# doodle_with_onboard_clock.net
KiCad netlist of a schematic drawn in EAGLE
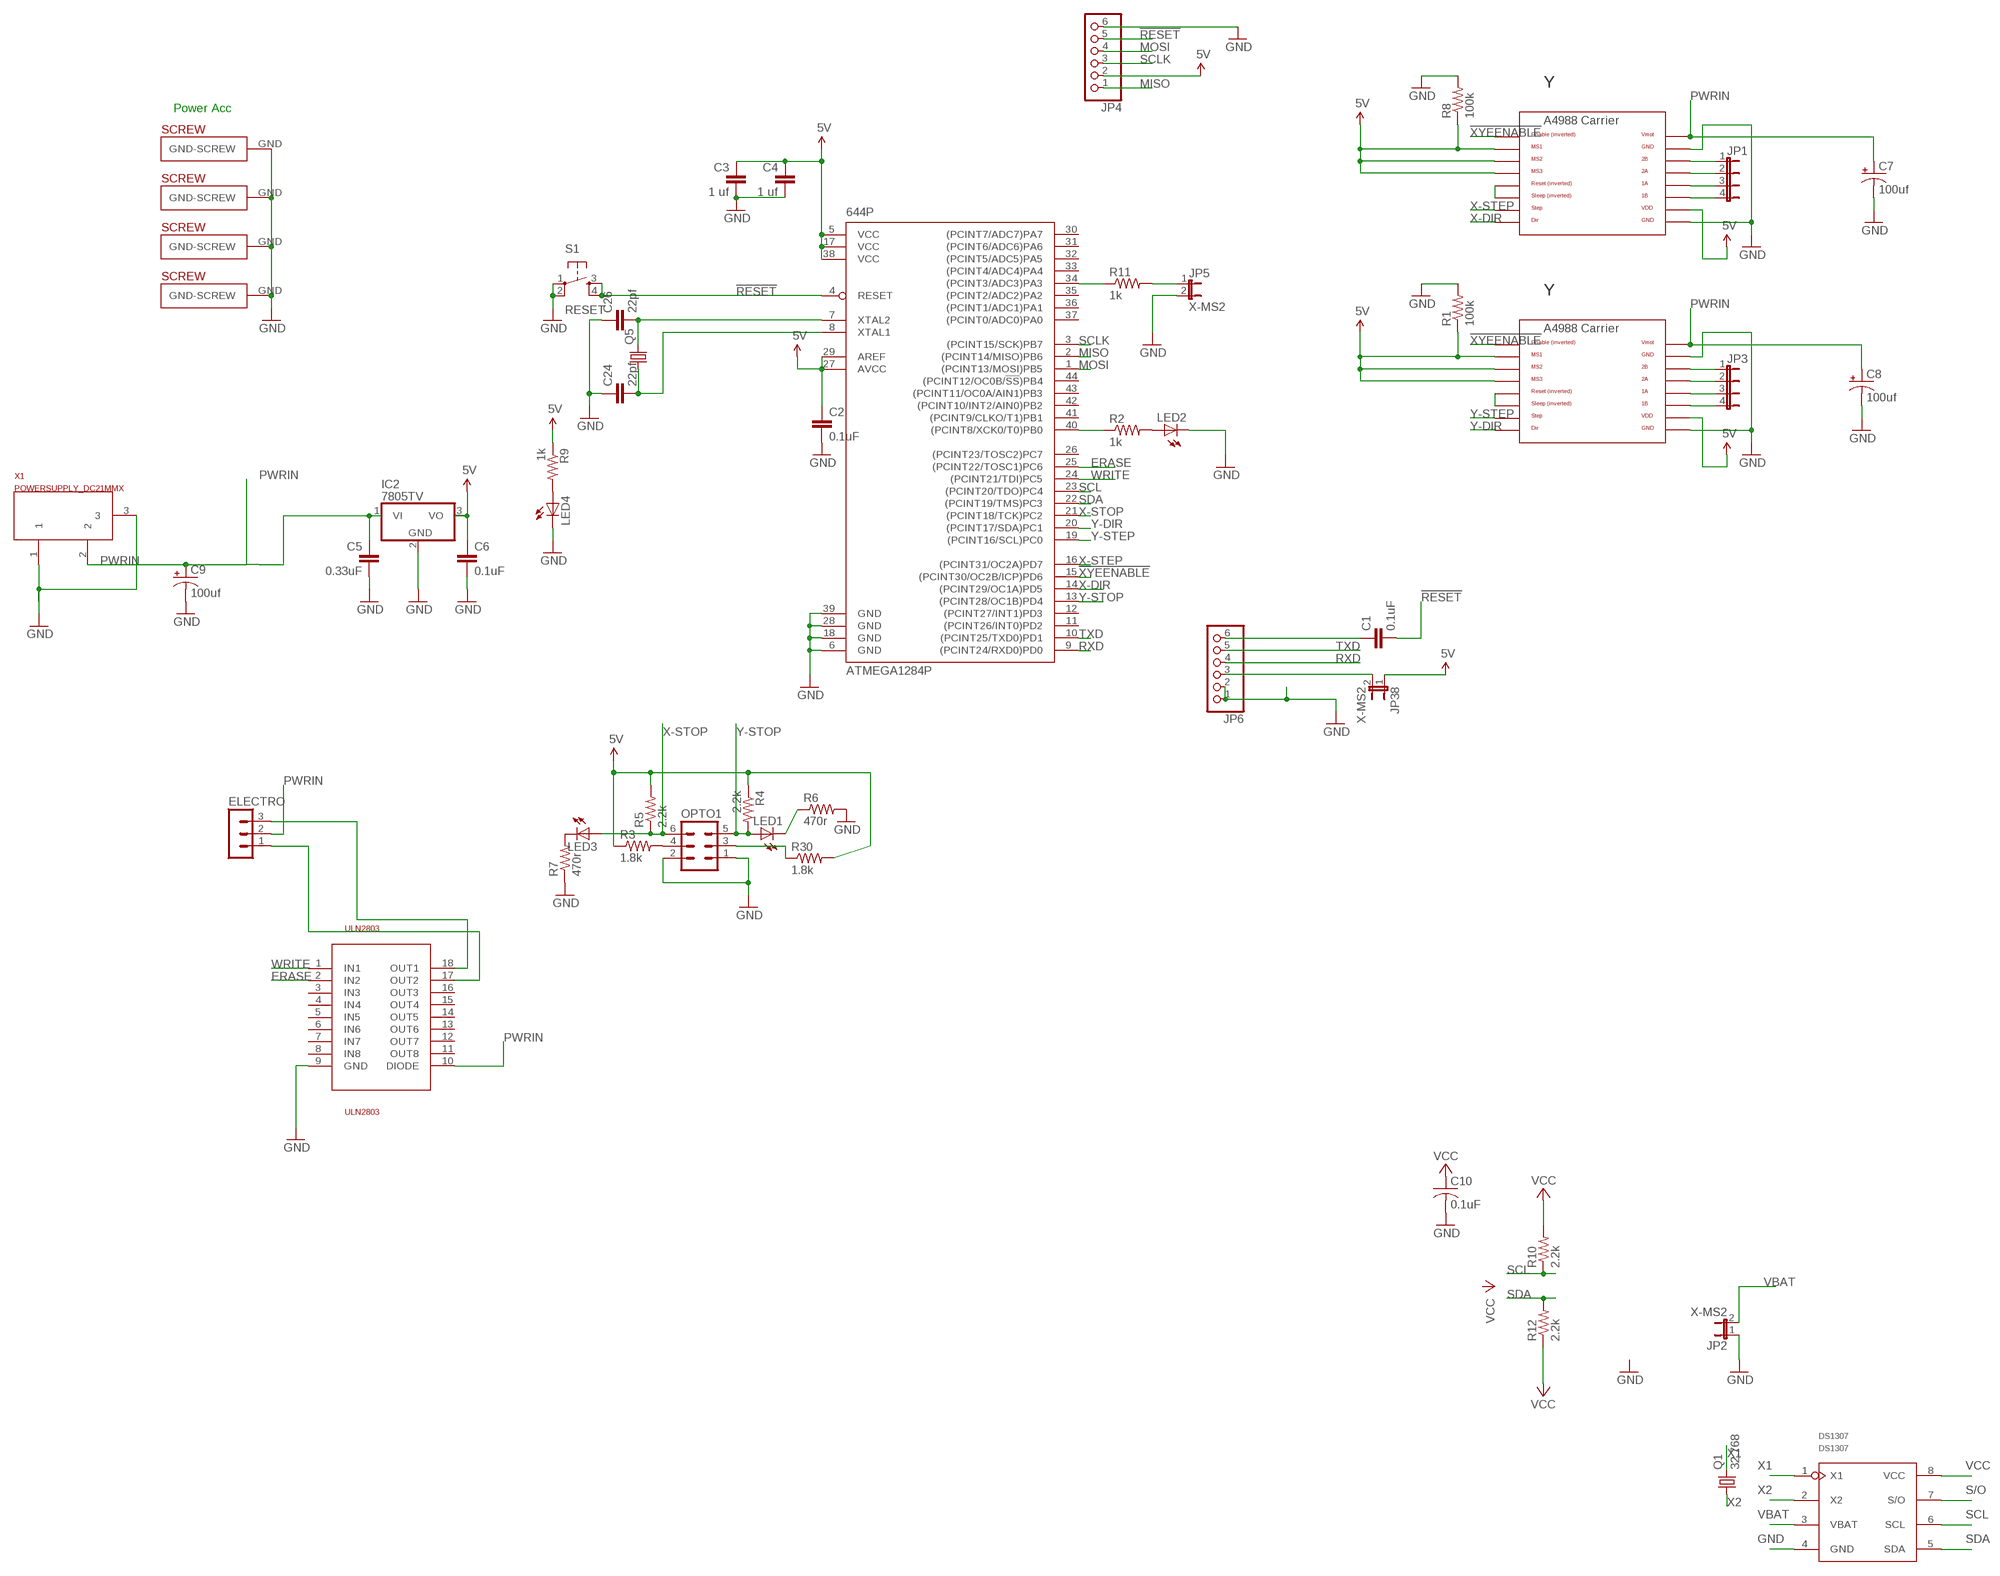
[diagram p0: schematic, sheet 1]

(export (version "E")
  (design (tool "Eeschema 10.0.6"))
  (components
    (comp (ref "644P")
      (value "ATMEGA1284P")
      (footprint "eagle-import:TQFP44")
      (fields (field (name "MPN") "ATMEGA644PV-10AU"))
      (libsource (lib "eagle-import") (part "ATMEGA644A"))
    )
    (comp (ref "C1")
      (value "0.1uF")
      (footprint "eagle-import:0805")
      (libsource (lib "eagle-import") (part "CAP0805"))
    )
    (comp (ref "C2")
      (value "0.1uF")
      (footprint "eagle-import:0805")
      (libsource (lib "eagle-import") (part "CAP0805"))
    )
    (comp (ref "C3")
      (value "1 uf")
      (footprint "eagle-import:0805")
      (libsource (lib "eagle-import") (part "CAP0805"))
    )
    (comp (ref "C4")
      (value "1 uf")
      (footprint "eagle-import:0805")
      (libsource (lib "eagle-import") (part "CAP0805"))
    )
    (comp (ref "C5")
      (value "0.33uF")
      (footprint "eagle-import:CAP-PTH-SMALL2")
      (libsource (lib "eagle-import") (part "CAPPTH2"))
    )
    (comp (ref "C6")
      (value "0.1uF")
      (footprint "eagle-import:CAP-PTH-SMALL2")
      (libsource (lib "eagle-import") (part "CAPPTH2"))
    )
    (comp (ref "C7")
      (value "100uf")
      (footprint "eagle-import:CPOL-RADIAL-100UF-25V")
      (libsource (lib "eagle-import") (part "CAP_POLPTH1"))
    )
    (comp (ref "C8")
      (value "100uf")
      (footprint "eagle-import:CPOL-RADIAL-100UF-25V")
      (libsource (lib "eagle-import") (part "CAP_POLPTH1"))
    )
    (comp (ref "C9")
      (value "100uf")
      (footprint "eagle-import:CPOL-RADIAL-100UF-25V")
      (libsource (lib "eagle-import") (part "CAP_POLPTH1"))
    )
    (comp (ref "C10")
      (value "0.1uF")
      (footprint "eagle-import:C0805")
      (libsource (lib "eagle-import") (part "C-USC0805"))
    )
    (comp (ref "C24")
      (value "22pf")
      (footprint "eagle-import:0805")
      (libsource (lib "eagle-import") (part "CAP0805"))
    )
    (comp (ref "C26")
      (value "22pf")
      (footprint "eagle-import:0805")
      (libsource (lib "eagle-import") (part "CAP0805"))
    )
    (comp (ref "DS1307")
      (value "DS1307")
      (footprint "eagle-import:SO08")
      (libsource (lib "eagle-import") (part "DS1307"))
    )
    (comp (ref "ELECTRO")
      (value "MA03-1")
      (footprint "eagle-import:MA03-1")
      (libsource (lib "eagle-import") (part "MA03-1"))
    )
    (comp (ref "IC2")
      (value "7805TV")
      (footprint "eagle-import:TO220V")
      (libsource (lib "eagle-import") (part "78TV05"))
    )
    (comp (ref "JP1")
      (value "JP4E")
      (footprint "eagle-import:JP4")
      (libsource (lib "eagle-import") (part "JP4E"))
    )
    (comp (ref "JP2")
      (value "X-MS2")
      (footprint "eagle-import:1X02")
      (libsource (lib "eagle-import") (part "JUMPER-2PTH"))
    )
    (comp (ref "JP3")
      (value "JP4E")
      (footprint "eagle-import:JP4")
      (libsource (lib "eagle-import") (part "JP4E"))
    )
    (comp (ref "JP4")
      (value "PINHD-1X6/90")
      (footprint "eagle-import:1X06_90")
      (libsource (lib "eagle-import") (part "PINHD-1X6/90"))
    )
    (comp (ref "JP5")
      (value "X-MS2")
      (footprint "eagle-import:1X02")
      (libsource (lib "eagle-import") (part "JUMPER-2PTH"))
    )
    (comp (ref "JP6")
      (value "PINHD-1X6")
      (footprint "eagle-import:1X06")
      (libsource (lib "eagle-import") (part "PINHD-1X6"))
    )
    (comp (ref "JP38")
      (value "X-MS2")
      (footprint "eagle-import:1X02")
      (libsource (lib "eagle-import") (part "JUMPER-2PTH"))
    )
    (comp (ref "LED1")
      (value "LEDCHIPLED_0805")
      (footprint "eagle-import:CHIPLED_0805")
      (libsource (lib "eagle-import") (part "LEDCHIPLED_0805"))
    )
    (comp (ref "LED2")
      (value "LEDCHIPLED_0805")
      (footprint "eagle-import:CHIPLED_0805")
      (libsource (lib "eagle-import") (part "LEDCHIPLED_0805"))
    )
    (comp (ref "LED3")
      (value "LEDCHIPLED_0805")
      (footprint "eagle-import:CHIPLED_0805")
      (libsource (lib "eagle-import") (part "LEDCHIPLED_0805"))
    )
    (comp (ref "LED4")
      (value "LEDCHIPLED_0805")
      (footprint "eagle-import:CHIPLED_0805")
      (libsource (lib "eagle-import") (part "LEDCHIPLED_0805"))
    )
    (comp (ref "OPTO1")
      (value "MA03-2")
      (footprint "eagle-import:MA03-2")
      (libsource (lib "eagle-import") (part "MA03-2"))
    )
    (comp (ref "Q1")
      (value "32.768")
      (footprint "eagle-import:TC38H")
      (libsource (lib "eagle-import") (part "CRYTALTC38H"))
    )
    (comp (ref "Q5")
      (value "CRYSTALHC49S")
      (footprint "eagle-import:HC49_S")
      (libsource (lib "eagle-import") (part "CRYSTALHC49S"))
    )
    (comp (ref "R1")
      (value "100k")
      (footprint "eagle-import:0207_7")
      (libsource (lib "eagle-import") (part "R-US_0207/7"))
    )
    (comp (ref "R2")
      (value "1k")
      (footprint "eagle-import:R0805")
      (libsource (lib "eagle-import") (part "resistor_R-US_R0805"))
    )
    (comp (ref "R3")
      (value "1.8k")
      (footprint "eagle-import:R0805")
      (libsource (lib "eagle-import") (part "resistor_R-US_R0805"))
    )
    (comp (ref "R4")
      (value "2.2k")
      (footprint "eagle-import:R0805")
      (libsource (lib "eagle-import") (part "resistor_R-US_R0805"))
    )
    (comp (ref "R5")
      (value "2.2k")
      (footprint "eagle-import:R0805")
      (libsource (lib "eagle-import") (part "resistor_R-US_R0805"))
    )
    (comp (ref "R6")
      (value "470r")
      (footprint "eagle-import:R0805")
      (libsource (lib "eagle-import") (part "resistor_R-US_R0805"))
    )
    (comp (ref "R7")
      (value "470r")
      (footprint "eagle-import:R0805")
      (libsource (lib "eagle-import") (part "resistor_R-US_R0805"))
    )
    (comp (ref "R8")
      (value "100k")
      (footprint "eagle-import:0207_7")
      (libsource (lib "eagle-import") (part "R-US_0207/7"))
    )
    (comp (ref "R9")
      (value "1k")
      (footprint "eagle-import:R0805")
      (libsource (lib "eagle-import") (part "resistor_R-US_R0805"))
    )
    (comp (ref "R10")
      (value "2.2k")
      (footprint "eagle-import:R0805")
      (libsource (lib "eagle-import") (part "resistor_R-US_R0805"))
    )
    (comp (ref "R11")
      (value "1k")
      (footprint "eagle-import:R0805")
      (libsource (lib "eagle-import") (part "resistor_R-US_R0805"))
    )
    (comp (ref "R12")
      (value "2.2k")
      (footprint "eagle-import:R0805")
      (libsource (lib "eagle-import") (part "resistor_R-US_R0805"))
    )
    (comp (ref "R30")
      (value "1.8k")
      (footprint "eagle-import:R0603")
      (libsource (lib "eagle-import") (part "resistor_R-US_R0603"))
    )
    (comp (ref "S1")
      (value "RESET")
      (footprint "eagle-import:TACTILE-PTH")
      (libsource (lib "eagle-import") (part "TAC_SWITCHPTH"))
    )
    (comp (ref "U$1")
      (value "A4988BREAKOUT")
      (footprint "eagle-import:A4988BREAKOUT")
      (libsource (lib "eagle-import") (part "A4988BREAKOUT"))
    )
    (comp (ref "U$7")
      (value "A4988BREAKOUT")
      (footprint "eagle-import:A4988BREAKOUT")
      (libsource (lib "eagle-import") (part "A4988BREAKOUT"))
    )
    (comp (ref "U$14")
      (value "PLATED-SCREW")
      (footprint "eagle-import:PLATEDSCREW")
      (libsource (lib "eagle-import") (part "PLATED-SCREW"))
    )
    (comp (ref "U$17")
      (value "PLATED-SCREW")
      (footprint "eagle-import:PLATEDSCREW")
      (libsource (lib "eagle-import") (part "PLATED-SCREW"))
    )
    (comp (ref "U$18")
      (value "PLATED-SCREW")
      (footprint "eagle-import:PLATEDSCREW")
      (libsource (lib "eagle-import") (part "PLATED-SCREW"))
    )
    (comp (ref "U$38")
      (value "PLATED-SCREW")
      (footprint "eagle-import:PLATEDSCREW")
      (libsource (lib "eagle-import") (part "PLATED-SCREW"))
    )
    (comp (ref "ULN2803")
      (value "ULN2803")
      (footprint "eagle-import:SO18L")
      (libsource (lib "eagle-import") (part "ULN2803"))
    )
    (comp (ref "X1")
      (value "POWERSUPPLY_DC21MMX")
      (footprint "eagle-import:POWERSUPPLY_DC-21MM")
      (libsource (lib "eagle-import") (part "POWERSUPPLY_DC21MMX"))
    )
  )
  (nets
    (net (code "1") (name "/ERASE") (class "Default")
      (node (ref "644P") (pin "25") (pinfunction "(PCINT22/TOSC1)PC6_25") (pintype "output"))
      (node (ref "ULN2803") (pin "2") (pinfunction "IN2_2") (pintype "input"))
    )
    (net (code "2") (name "/MISO") (class "Default")
      (node (ref "644P") (pin "2") (pinfunction "(PCINT14/MISO)PB6_2") (pintype "bidirectional"))
      (node (ref "JP4") (pin "1") (pinfunction "1_1") (pintype "passive"))
    )
    (net (code "3") (name "/MOSI") (class "Default")
      (node (ref "644P") (pin "1") (pinfunction "(PCINT13/MOSI)PB5_1") (pintype "bidirectional"))
      (node (ref "JP4") (pin "4") (pinfunction "4_4") (pintype "passive"))
    )
    (net (code "4") (name "/PWRIN") (class "Default")
      (node (ref "C5") (pin "1") (pinfunction "1_1") (pintype "passive"))
      (node (ref "C7") (pin "1") (pinfunction "+_1") (pintype "passive"))
      (node (ref "C8") (pin "1") (pinfunction "+_1") (pintype "passive"))
      (node (ref "C9") (pin "1") (pinfunction "+_1") (pintype "passive"))
      (node (ref "ELECTRO") (pin "2") (pinfunction "2_2") (pintype "passive"))
      (node (ref "IC2") (pin "1") (pinfunction "VI_1") (pintype "input"))
      (node (ref "U$1") (pin "VMOT") (pinfunction "VMOT_VMOT") (pintype "power_in"))
      (node (ref "U$7") (pin "VMOT") (pinfunction "VMOT_VMOT") (pintype "power_in"))
      (node (ref "ULN2803") (pin "10") (pinfunction "DIODE_10") (pintype "power_in"))
      (node (ref "X1") (pin "2") (pinfunction "2_2") (pintype "power_in"))
    )
    (net (code "5") (name "/RXD") (class "Default")
      (node (ref "644P") (pin "9") (pinfunction "(PCINT24/RXD0)PD0_9") (pintype "bidirectional"))
      (node (ref "JP6") (pin "4") (pinfunction "4_4") (pintype "passive"))
    )
    (net (code "6") (name "/SCL") (class "Default")
      (node (ref "644P") (pin "23") (pinfunction "(PCINT20/TDO)PC4_23") (pintype "output"))
      (node (ref "DS1307") (pin "6") (pinfunction "SCL_6") (pintype "bidirectional"))
      (node (ref "R10") (pin "1") (pinfunction "1_1") (pintype "passive"))
    )
    (net (code "7") (name "/SCLK") (class "Default")
      (node (ref "644P") (pin "3") (pinfunction "(PCINT15/SCK)PB7_3") (pintype "bidirectional"))
      (node (ref "JP4") (pin "3") (pinfunction "3_3") (pintype "passive"))
    )
    (net (code "8") (name "/SDA") (class "Default")
      (node (ref "644P") (pin "22") (pinfunction "(PCINT19/TMS)PC3_22") (pintype "output"))
      (node (ref "DS1307") (pin "5") (pinfunction "SDA_5") (pintype "bidirectional"))
      (node (ref "R12") (pin "2") (pinfunction "2_2") (pintype "passive"))
    )
    (net (code "9") (name "/S{slash}O") (class "Default")
      (node (ref "DS1307") (pin "7") (pinfunction "S/O_7") (pintype "bidirectional"))
    )
    (net (code "10") (name "/TXD") (class "Default")
      (node (ref "644P") (pin "10") (pinfunction "(PCINT25/TXD0)PD1_10") (pintype "bidirectional"))
      (node (ref "JP6") (pin "5") (pinfunction "5_5") (pintype "passive"))
    )
    (net (code "11") (name "/VBAT") (class "Default")
      (node (ref "DS1307") (pin "3") (pinfunction "VBAT_3") (pintype "bidirectional"))
      (node (ref "JP2") (pin "2") (pinfunction "2_2") (pintype "passive"))
    )
    (net (code "12") (name "/WRITE") (class "Default")
      (node (ref "644P") (pin "24") (pinfunction "(PCINT21/TDI)PC5_24") (pintype "output"))
      (node (ref "ULN2803") (pin "1") (pinfunction "IN1_1") (pintype "input"))
    )
    (net (code "13") (name "/X-DIR") (class "Default")
      (node (ref "644P") (pin "14") (pinfunction "(PCINT29/OC1A)PD5_14") (pintype "bidirectional"))
      (node (ref "U$7") (pin "DIR") (pinfunction "DIR_DIR") (pintype "input"))
    )
    (net (code "14") (name "/X-STEP") (class "Default")
      (node (ref "644P") (pin "16") (pinfunction "(PCINT31/OC2A)PD7_16") (pintype "bidirectional"))
      (node (ref "U$7") (pin "STEP") (pinfunction "STEP_STEP") (pintype "input"))
    )
    (net (code "15") (name "/X-STOP") (class "Default")
      (node (ref "644P") (pin "21") (pinfunction "(PCINT18/TCK)PC2_21") (pintype "output"))
      (node (ref "LED3") (pin "A") (pinfunction "A_A") (pintype "passive"))
      (node (ref "OPTO1") (pin "6") (pinfunction "6_6") (pintype "passive"))
      (node (ref "R5") (pin "1") (pinfunction "1_1") (pintype "passive"))
    )
    (net (code "16") (name "/X1") (class "Default")
      (node (ref "DS1307") (pin "1") (pinfunction "X1_1") (pintype "bidirectional"))
      (node (ref "Q1") (pin "2") (pinfunction "2_2") (pintype "passive"))
    )
    (net (code "17") (name "/X2") (class "Default")
      (node (ref "DS1307") (pin "2") (pinfunction "X2_2") (pintype "bidirectional"))
      (node (ref "Q1") (pin "1") (pinfunction "1_1") (pintype "passive"))
    )
    (net (code "18") (name "/Y-DIR") (class "Default")
      (node (ref "644P") (pin "20") (pinfunction "(PCINT17/SDA)PC1_20") (pintype "output"))
      (node (ref "U$1") (pin "DIR") (pinfunction "DIR_DIR") (pintype "input"))
    )
    (net (code "19") (name "/Y-STEP") (class "Default")
      (node (ref "644P") (pin "19") (pinfunction "(PCINT16/SCL)PC0_19") (pintype "output"))
      (node (ref "U$1") (pin "STEP") (pinfunction "STEP_STEP") (pintype "input"))
    )
    (net (code "20") (name "/Y-STOP") (class "Default")
      (node (ref "644P") (pin "13") (pinfunction "(PCINT28/OC1B)PD4_13") (pintype "bidirectional"))
      (node (ref "LED1") (pin "A") (pinfunction "A_A") (pintype "passive"))
      (node (ref "OPTO1") (pin "5") (pinfunction "5_5") (pintype "passive"))
      (node (ref "R4") (pin "2") (pinfunction "2_2") (pintype "passive"))
    )
    (net (code "21") (name "/~{RESET}") (class "Default")
      (node (ref "644P") (pin "4") (pinfunction "RESET_4") (pintype "input"))
      (node (ref "C1") (pin "2") (pinfunction "2_2") (pintype "passive"))
      (node (ref "JP4") (pin "5") (pinfunction "5_5") (pintype "passive"))
      (node (ref "S1") (pin "3") (pinfunction "3_3") (pintype "passive"))
      (node (ref "S1") (pin "4") (pinfunction "4_4") (pintype "passive"))
    )
    (net (code "22") (name "/~{XYEENABLE}") (class "Default")
      (node (ref "644P") (pin "15") (pinfunction "(PCINT30/OC2B/ICP)PD6_15") (pintype "bidirectional"))
      (node (ref "U$1") (pin "EN") (pinfunction "EN_EN") (pintype "input"))
      (node (ref "U$7") (pin "EN") (pinfunction "EN_EN") (pintype "input"))
    )
    (net (code "23") (name "5V") (class "Default")
      (node (ref "644P") (pin "17") (pinfunction "VCC_17") (pintype "power_in"))
      (node (ref "644P") (pin "27") (pinfunction "AVCC_27") (pintype "power_in"))
      (node (ref "644P") (pin "29") (pinfunction "AREF_29") (pintype "passive"))
      (node (ref "644P") (pin "38") (pinfunction "VCC_38") (pintype "power_in"))
      (node (ref "644P") (pin "5") (pinfunction "VCC_5") (pintype "power_in"))
      (node (ref "C2") (pin "1") (pinfunction "1_1") (pintype "passive"))
      (node (ref "C3") (pin "1") (pinfunction "1_1") (pintype "passive"))
      (node (ref "C4") (pin "1") (pinfunction "1_1") (pintype "passive"))
      (node (ref "C6") (pin "1") (pinfunction "1_1") (pintype "passive"))
      (node (ref "IC2") (pin "3") (pinfunction "VO_3") (pintype "passive"))
      (node (ref "JP38") (pin "1") (pinfunction "1_1") (pintype "passive"))
      (node (ref "JP4") (pin "2") (pinfunction "2_2") (pintype "passive"))
      (node (ref "R1") (pin "1") (pinfunction "1_1") (pintype "passive"))
      (node (ref "R3") (pin "1") (pinfunction "1_1") (pintype "passive"))
      (node (ref "R30") (pin "2") (pinfunction "2_2") (pintype "passive"))
      (node (ref "R4") (pin "1") (pinfunction "1_1") (pintype "passive"))
      (node (ref "R5") (pin "2") (pinfunction "2_2") (pintype "passive"))
      (node (ref "R8") (pin "1") (pinfunction "1_1") (pintype "passive"))
      (node (ref "R9") (pin "1") (pinfunction "1_1") (pintype "passive"))
      (node (ref "U$1") (pin "MS1") (pinfunction "MS1_MS1") (pintype "input"))
      (node (ref "U$1") (pin "MS2") (pinfunction "MS2_MS2") (pintype "input"))
      (node (ref "U$1") (pin "MS3") (pinfunction "MS3_MS3") (pintype "input"))
      (node (ref "U$1") (pin "VDD") (pinfunction "VDD_VDD") (pintype "power_in"))
      (node (ref "U$7") (pin "MS1") (pinfunction "MS1_MS1") (pintype "input"))
      (node (ref "U$7") (pin "MS2") (pinfunction "MS2_MS2") (pintype "input"))
      (node (ref "U$7") (pin "MS3") (pinfunction "MS3_MS3") (pintype "input"))
      (node (ref "U$7") (pin "VDD") (pinfunction "VDD_VDD") (pintype "power_in"))
    )
    (net (code "24") (name "GND") (class "Default")
      (node (ref "644P") (pin "18") (pinfunction "GND_18") (pintype "power_in"))
      (node (ref "644P") (pin "28") (pinfunction "GND_28") (pintype "power_in"))
      (node (ref "644P") (pin "39") (pinfunction "GND_39") (pintype "power_in"))
      (node (ref "644P") (pin "6") (pinfunction "GND_6") (pintype "power_in"))
      (node (ref "C10") (pin "2") (pinfunction "2_2") (pintype "passive"))
      (node (ref "C2") (pin "2") (pinfunction "2_2") (pintype "passive"))
      (node (ref "C24") (pin "1") (pinfunction "1_1") (pintype "passive"))
      (node (ref "C26") (pin "1") (pinfunction "1_1") (pintype "passive"))
      (node (ref "C3") (pin "2") (pinfunction "2_2") (pintype "passive"))
      (node (ref "C4") (pin "2") (pinfunction "2_2") (pintype "passive"))
      (node (ref "C5") (pin "2") (pinfunction "2_2") (pintype "passive"))
      (node (ref "C6") (pin "2") (pinfunction "2_2") (pintype "passive"))
      (node (ref "C7") (pin "2") (pinfunction "-_2") (pintype "passive"))
      (node (ref "C8") (pin "2") (pinfunction "-_2") (pintype "passive"))
      (node (ref "C9") (pin "2") (pinfunction "-_2") (pintype "passive"))
      (node (ref "DS1307") (pin "4") (pinfunction "GND_4") (pintype "bidirectional"))
      (node (ref "IC2") (pin "2") (pinfunction "GND_2") (pintype "passive"))
      (node (ref "JP2") (pin "1") (pinfunction "1_1") (pintype "passive"))
      (node (ref "JP4") (pin "6") (pinfunction "6_6") (pintype "passive"))
      (node (ref "JP5") (pin "2") (pinfunction "2_2") (pintype "passive"))
      (node (ref "JP6") (pin "1") (pinfunction "1_1") (pintype "passive"))
      (node (ref "JP6") (pin "2") (pinfunction "2_2") (pintype "passive"))
      (node (ref "LED2") (pin "C") (pinfunction "C_C") (pintype "passive"))
      (node (ref "LED4") (pin "C") (pinfunction "C_C") (pintype "passive"))
      (node (ref "OPTO1") (pin "1") (pinfunction "1_1") (pintype "passive"))
      (node (ref "OPTO1") (pin "2") (pinfunction "2_2") (pintype "passive"))
      (node (ref "R1") (pin "2") (pinfunction "2_2") (pintype "passive"))
      (node (ref "R6") (pin "2") (pinfunction "2_2") (pintype "passive"))
      (node (ref "R7") (pin "1") (pinfunction "1_1") (pintype "passive"))
      (node (ref "R8") (pin "2") (pinfunction "2_2") (pintype "passive"))
      (node (ref "S1") (pin "1") (pinfunction "1_1") (pintype "passive"))
      (node (ref "S1") (pin "2") (pinfunction "2_2") (pintype "passive"))
      (node (ref "U$1") (pin "GND") (pinfunction "GND_GND") (pintype "power_in"))
      (node (ref "U$1") (pin "GND@0") (pinfunction "GND_GND@0") (pintype "power_in"))
      (node (ref "U$14") (pin "GND") (pinfunction "GND-SCREW_GND") (pintype "bidirectional"))
      (node (ref "U$17") (pin "GND") (pinfunction "GND-SCREW_GND") (pintype "bidirectional"))
      (node (ref "U$18") (pin "GND") (pinfunction "GND-SCREW_GND") (pintype "bidirectional"))
      (node (ref "U$38") (pin "GND") (pinfunction "GND-SCREW_GND") (pintype "bidirectional"))
      (node (ref "U$7") (pin "GND") (pinfunction "GND_GND") (pintype "power_in"))
      (node (ref "U$7") (pin "GND@0") (pinfunction "GND_GND@0") (pintype "power_in"))
      (node (ref "ULN2803") (pin "9") (pinfunction "GND_9") (pintype "power_in"))
      (node (ref "X1") (pin "1") (pinfunction "1_1") (pintype "power_in"))
      (node (ref "X1") (pin "3") (pinfunction "3_3") (pintype "power_in"))
    )
    (net (code "25") (name "Net-(644P-(PCINT3{slash}ADC3)PA3)") (class "Default")
      (node (ref "644P") (pin "34") (pinfunction "(PCINT3/ADC3)PA3_34") (pintype "bidirectional"))
      (node (ref "R11") (pin "1") (pinfunction "1_1") (pintype "passive"))
    )
    (net (code "26") (name "Net-(644P-(PCINT8{slash}XCK0{slash}T0)PB0)") (class "Default")
      (node (ref "644P") (pin "40") (pinfunction "(PCINT8/XCK0/T0)PB0_40") (pintype "bidirectional"))
      (node (ref "R2") (pin "1") (pinfunction "1_1") (pintype "passive"))
    )
    (net (code "27") (name "Net-(644P-XTAL1)") (class "Default")
      (node (ref "644P") (pin "8") (pinfunction "XTAL1_8") (pintype "bidirectional"))
      (node (ref "C24") (pin "2") (pinfunction "2_2") (pintype "passive"))
      (node (ref "Q5") (pin "1") (pinfunction "1_1") (pintype "passive"))
    )
    (net (code "28") (name "Net-(644P-XTAL2)") (class "Default")
      (node (ref "644P") (pin "7") (pinfunction "XTAL2_7") (pintype "bidirectional"))
      (node (ref "C26") (pin "2") (pinfunction "2_2") (pintype "passive"))
      (node (ref "Q5") (pin "2") (pinfunction "2_2") (pintype "passive"))
    )
    (net (code "29") (name "Net-(C1-Pad1)") (class "Default")
      (node (ref "C1") (pin "1") (pinfunction "1_1") (pintype "passive"))
      (node (ref "JP6") (pin "6") (pinfunction "6_6") (pintype "passive"))
    )
    (net (code "30") (name "Net-(JP1-Pad1)") (class "Default")
      (node (ref "JP1") (pin "1") (pinfunction "1_1") (pintype "passive"))
      (node (ref "U$7") (pin "2B") (pinfunction "2B_2B") (pintype "output"))
    )
    (net (code "31") (name "Net-(JP1-Pad2)") (class "Default")
      (node (ref "JP1") (pin "2") (pinfunction "2_2") (pintype "passive"))
      (node (ref "U$7") (pin "2A") (pinfunction "2A_2A") (pintype "output"))
    )
    (net (code "32") (name "Net-(JP1-Pad3)") (class "Default")
      (node (ref "JP1") (pin "3") (pinfunction "3_3") (pintype "passive"))
      (node (ref "U$7") (pin "1A") (pinfunction "1A_1A") (pintype "output"))
    )
    (net (code "33") (name "Net-(JP1-Pad4)") (class "Default")
      (node (ref "JP1") (pin "4") (pinfunction "4_4") (pintype "passive"))
      (node (ref "U$7") (pin "1B") (pinfunction "1B_1B") (pintype "output"))
    )
    (net (code "34") (name "Net-(JP3-Pad1)") (class "Default")
      (node (ref "JP3") (pin "1") (pinfunction "1_1") (pintype "passive"))
      (node (ref "U$1") (pin "2B") (pinfunction "2B_2B") (pintype "output"))
    )
    (net (code "35") (name "Net-(JP3-Pad2)") (class "Default")
      (node (ref "JP3") (pin "2") (pinfunction "2_2") (pintype "passive"))
      (node (ref "U$1") (pin "2A") (pinfunction "2A_2A") (pintype "output"))
    )
    (net (code "36") (name "Net-(JP3-Pad3)") (class "Default")
      (node (ref "JP3") (pin "3") (pinfunction "3_3") (pintype "passive"))
      (node (ref "U$1") (pin "1A") (pinfunction "1A_1A") (pintype "output"))
    )
    (net (code "37") (name "Net-(JP3-Pad4)") (class "Default")
      (node (ref "JP3") (pin "4") (pinfunction "4_4") (pintype "passive"))
      (node (ref "U$1") (pin "1B") (pinfunction "1B_1B") (pintype "output"))
    )
    (net (code "38") (name "Net-(JP5-Pad1)") (class "Default")
      (node (ref "JP5") (pin "1") (pinfunction "1_1") (pintype "passive"))
      (node (ref "R11") (pin "2") (pinfunction "2_2") (pintype "passive"))
    )
    (net (code "39") (name "Net-(JP38-Pad2)") (class "Default")
      (node (ref "JP38") (pin "2") (pinfunction "2_2") (pintype "passive"))
      (node (ref "JP6") (pin "3") (pinfunction "3_3") (pintype "passive"))
    )
    (net (code "40") (name "Net-(LED1-PadC)") (class "Default")
      (node (ref "LED1") (pin "C") (pinfunction "C_C") (pintype "passive"))
      (node (ref "R6") (pin "1") (pinfunction "1_1") (pintype "passive"))
    )
    (net (code "41") (name "Net-(LED2-PadA)") (class "Default")
      (node (ref "LED2") (pin "A") (pinfunction "A_A") (pintype "passive"))
      (node (ref "R2") (pin "2") (pinfunction "2_2") (pintype "passive"))
    )
    (net (code "42") (name "Net-(LED3-PadC)") (class "Default")
      (node (ref "LED3") (pin "C") (pinfunction "C_C") (pintype "passive"))
      (node (ref "R7") (pin "2") (pinfunction "2_2") (pintype "passive"))
    )
    (net (code "43") (name "Net-(LED4-PadA)") (class "Default")
      (node (ref "LED4") (pin "A") (pinfunction "A_A") (pintype "passive"))
      (node (ref "R9") (pin "2") (pinfunction "2_2") (pintype "passive"))
    )
    (net (code "44") (name "Net-(OPTO1-Pad3)") (class "Default")
      (node (ref "OPTO1") (pin "3") (pinfunction "3_3") (pintype "passive"))
      (node (ref "R30") (pin "1") (pinfunction "1_1") (pintype "passive"))
    )
    (net (code "45") (name "Net-(OPTO1-Pad4)") (class "Default")
      (node (ref "OPTO1") (pin "4") (pinfunction "4_4") (pintype "passive"))
      (node (ref "R3") (pin "2") (pinfunction "2_2") (pintype "passive"))
    )
    (net (code "46") (name "Net-(U$1-SLEEP)") (class "Default")
      (node (ref "U$1") (pin "RST") (pinfunction "RST_RST") (pintype "input"))
      (node (ref "U$1") (pin "SLP") (pinfunction "SLEEP_SLP") (pintype "input"))
    )
    (net (code "47") (name "Net-(U$7-SLEEP)") (class "Default")
      (node (ref "U$7") (pin "RST") (pinfunction "RST_RST") (pintype "input"))
      (node (ref "U$7") (pin "SLP") (pinfunction "SLEEP_SLP") (pintype "input"))
    )
    (net (code "48") (name "Net-(ULN2803-OUT1)") (class "Default")
      (node (ref "ELECTRO") (pin "3") (pinfunction "3_3") (pintype "passive"))
      (node (ref "ULN2803") (pin "18") (pinfunction "OUT1_18") (pintype "open_collector"))
    )
    (net (code "49") (name "Net-(ULN2803-OUT2)") (class "Default")
      (node (ref "ELECTRO") (pin "1") (pinfunction "1_1") (pintype "passive"))
      (node (ref "ULN2803") (pin "17") (pinfunction "OUT2_17") (pintype "open_collector"))
    )
    (net (code "50") (name "VCC") (class "Default")
      (node (ref "C10") (pin "1") (pinfunction "1_1") (pintype "passive"))
      (node (ref "DS1307") (pin "8") (pinfunction "VCC_8") (pintype "bidirectional"))
      (node (ref "R10") (pin "2") (pinfunction "2_2") (pintype "passive"))
      (node (ref "R12") (pin "1") (pinfunction "1_1") (pintype "passive"))
    )
    (net (code "51") (name "unconnected-(644P-(PCINT0{slash}ADC0)PA0-Pad37)") (class "Default")
      (node (ref "644P") (pin "37") (pinfunction "(PCINT0/ADC0)PA0_37") (pintype "bidirectional"))
    )
    (net (code "52") (name "unconnected-(644P-(PCINT1{slash}ADC1)PA1-Pad36)") (class "Default")
      (node (ref "644P") (pin "36") (pinfunction "(PCINT1/ADC1)PA1_36") (pintype "bidirectional"))
    )
    (net (code "53") (name "unconnected-(644P-(PCINT2{slash}ADC2)PA2-Pad35)") (class "Default")
      (node (ref "644P") (pin "35") (pinfunction "(PCINT2/ADC2)PA2_35") (pintype "bidirectional"))
    )
    (net (code "54") (name "unconnected-(644P-(PCINT4{slash}ADC4)PA4-Pad33)") (class "Default")
      (node (ref "644P") (pin "33") (pinfunction "(PCINT4/ADC4)PA4_33") (pintype "bidirectional"))
    )
    (net (code "55") (name "unconnected-(644P-(PCINT5{slash}ADC5)PA5-Pad32)") (class "Default")
      (node (ref "644P") (pin "32") (pinfunction "(PCINT5/ADC5)PA5_32") (pintype "bidirectional"))
    )
    (net (code "56") (name "unconnected-(644P-(PCINT6{slash}ADC6)PA6-Pad31)") (class "Default")
      (node (ref "644P") (pin "31") (pinfunction "(PCINT6/ADC6)PA6_31") (pintype "bidirectional"))
    )
    (net (code "57") (name "unconnected-(644P-(PCINT7{slash}ADC7)PA7-Pad30)") (class "Default")
      (node (ref "644P") (pin "30") (pinfunction "(PCINT7/ADC7)PA7_30") (pintype "bidirectional"))
    )
    (net (code "58") (name "unconnected-(644P-(PCINT9{slash}CLKO{slash}T1)PB1-Pad41)") (class "Default")
      (node (ref "644P") (pin "41") (pinfunction "(PCINT9/CLKO/T1)PB1_41") (pintype "bidirectional"))
    )
    (net (code "59") (name "unconnected-(644P-(PCINT10{slash}INT2{slash}AIN0)PB2-Pad42)") (class "Default")
      (node (ref "644P") (pin "42") (pinfunction "(PCINT10/INT2/AIN0)PB2_42") (pintype "bidirectional"))
    )
    (net (code "60") (name "unconnected-(644P-(PCINT11{slash}OC0A{slash}AIN1)PB3-Pad43)") (class "Default")
      (node (ref "644P") (pin "43") (pinfunction "(PCINT11/OC0A/AIN1)PB3_43") (pintype "bidirectional"))
    )
    (net (code "61") (name "unconnected-(644P-(PCINT12{slash}OC0B{slash}~{SS})PB4-Pad44)") (class "Default")
      (node (ref "644P") (pin "44") (pinfunction "(PCINT12/OC0B/~{SS})PB4_44") (pintype "bidirectional"))
    )
    (net (code "62") (name "unconnected-(644P-(PCINT23{slash}TOSC2)PC7-Pad26)") (class "Default")
      (node (ref "644P") (pin "26") (pinfunction "(PCINT23/TOSC2)PC7_26") (pintype "output"))
    )
    (net (code "63") (name "unconnected-(644P-(PCINT26{slash}INT0)PD2-Pad11)") (class "Default")
      (node (ref "644P") (pin "11") (pinfunction "(PCINT26/INT0)PD2_11") (pintype "bidirectional"))
    )
    (net (code "64") (name "unconnected-(644P-(PCINT27{slash}INT1)PD3-Pad12)") (class "Default")
      (node (ref "644P") (pin "12") (pinfunction "(PCINT27/INT1)PD3_12") (pintype "bidirectional"))
    )
    (net (code "65") (name "unconnected-(ULN2803-IN3-Pad3)") (class "Default")
      (node (ref "ULN2803") (pin "3") (pinfunction "IN3_3") (pintype "input"))
    )
    (net (code "66") (name "unconnected-(ULN2803-IN4-Pad4)") (class "Default")
      (node (ref "ULN2803") (pin "4") (pinfunction "IN4_4") (pintype "input"))
    )
    (net (code "67") (name "unconnected-(ULN2803-IN5-Pad5)") (class "Default")
      (node (ref "ULN2803") (pin "5") (pinfunction "IN5_5") (pintype "input"))
    )
    (net (code "68") (name "unconnected-(ULN2803-IN6-Pad6)") (class "Default")
      (node (ref "ULN2803") (pin "6") (pinfunction "IN6_6") (pintype "input"))
    )
    (net (code "69") (name "unconnected-(ULN2803-IN7-Pad7)") (class "Default")
      (node (ref "ULN2803") (pin "7") (pinfunction "IN7_7") (pintype "input"))
    )
    (net (code "70") (name "unconnected-(ULN2803-IN8-Pad8)") (class "Default")
      (node (ref "ULN2803") (pin "8") (pinfunction "IN8_8") (pintype "input"))
    )
    (net (code "71") (name "unconnected-(ULN2803-OUT3-Pad16)") (class "Default")
      (node (ref "ULN2803") (pin "16") (pinfunction "OUT3_16") (pintype "open_collector"))
    )
    (net (code "72") (name "unconnected-(ULN2803-OUT4-Pad15)") (class "Default")
      (node (ref "ULN2803") (pin "15") (pinfunction "OUT4_15") (pintype "open_collector"))
    )
    (net (code "73") (name "unconnected-(ULN2803-OUT5-Pad14)") (class "Default")
      (node (ref "ULN2803") (pin "14") (pinfunction "OUT5_14") (pintype "open_collector"))
    )
    (net (code "74") (name "unconnected-(ULN2803-OUT6-Pad13)") (class "Default")
      (node (ref "ULN2803") (pin "13") (pinfunction "OUT6_13") (pintype "open_collector"))
    )
    (net (code "75") (name "unconnected-(ULN2803-OUT7-Pad12)") (class "Default")
      (node (ref "ULN2803") (pin "12") (pinfunction "OUT7_12") (pintype "open_collector"))
    )
    (net (code "76") (name "unconnected-(ULN2803-OUT8-Pad11)") (class "Default")
      (node (ref "ULN2803") (pin "11") (pinfunction "OUT8_11") (pintype "open_collector"))
    )
  )
)
